# icbm_power_dpak.net
KiCad netlist of a schematic drawn in EAGLE
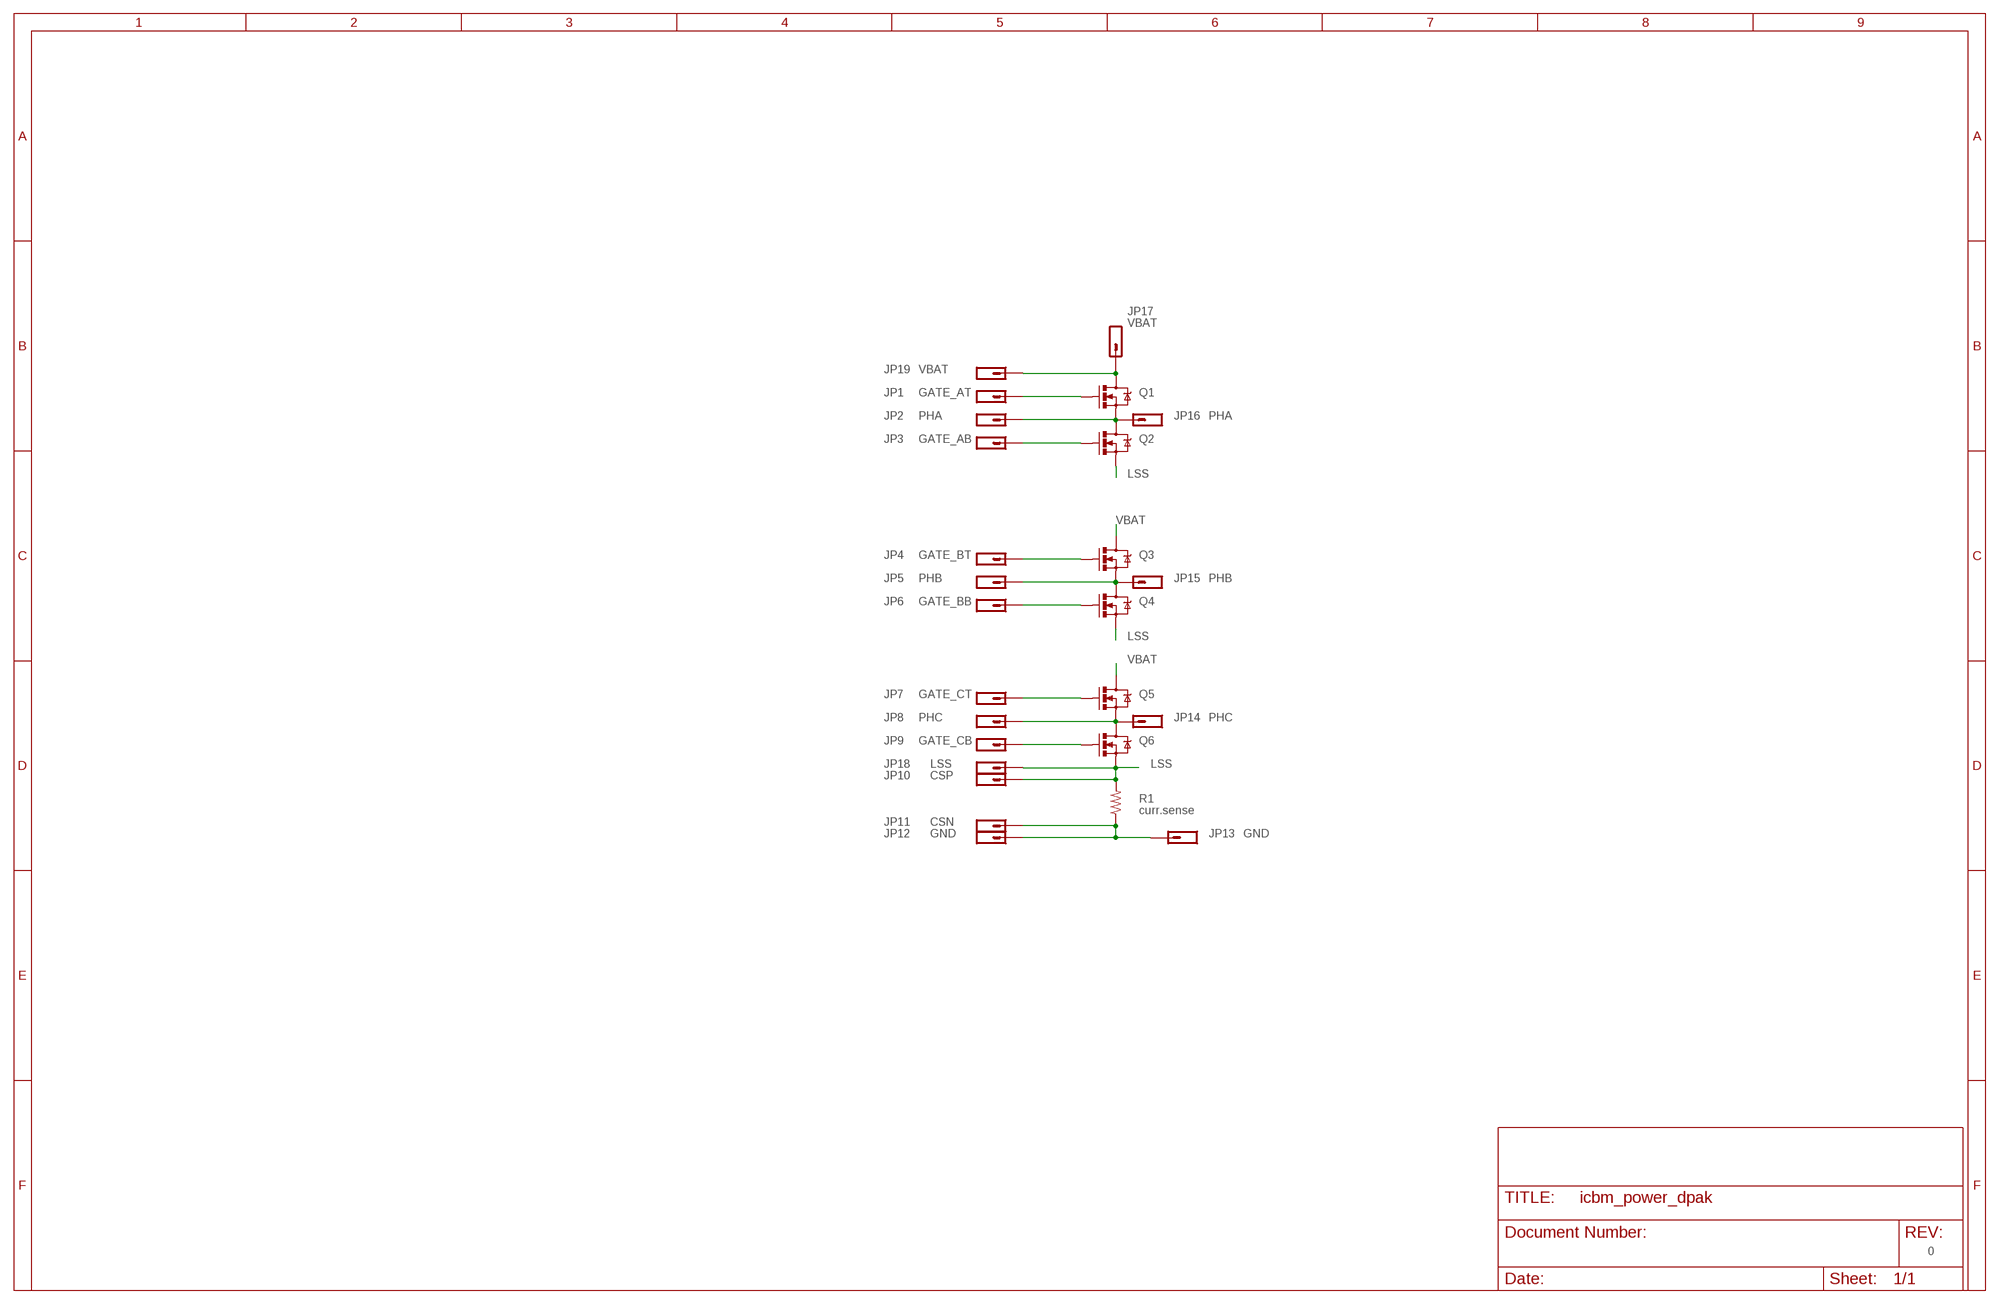
[diagram p0: schematic, sheet 1]

(export (version "E")
  (design (tool "Eeschema 10.0.6"))
  (components
    (comp (ref "JP1")
      (value "GATE_AT")
      (footprint "eagle-import:1X01_TT")
      (libsource (lib "eagle-import") (part "M01-TT"))
    )
    (comp (ref "JP2")
      (value "PHA")
      (footprint "eagle-import:1X01_TT")
      (libsource (lib "eagle-import") (part "M01-TT"))
    )
    (comp (ref "JP3")
      (value "GATE_AB")
      (footprint "eagle-import:1X01_TT")
      (libsource (lib "eagle-import") (part "M01-TT"))
    )
    (comp (ref "JP4")
      (value "GATE_BT")
      (footprint "eagle-import:1X01_TT")
      (libsource (lib "eagle-import") (part "M01-TT"))
    )
    (comp (ref "JP5")
      (value "PHB")
      (footprint "eagle-import:1X01_TT")
      (libsource (lib "eagle-import") (part "M01-TT"))
    )
    (comp (ref "JP6")
      (value "GATE_BB")
      (footprint "eagle-import:1X01_TT")
      (libsource (lib "eagle-import") (part "M01-TT"))
    )
    (comp (ref "JP7")
      (value "GATE_CT")
      (footprint "eagle-import:1X01_TT")
      (libsource (lib "eagle-import") (part "M01-TT"))
    )
    (comp (ref "JP8")
      (value "PHC")
      (footprint "eagle-import:1X01_TT")
      (libsource (lib "eagle-import") (part "M01-TT"))
    )
    (comp (ref "JP9")
      (value "GATE_CB")
      (footprint "eagle-import:1X01_TT")
      (libsource (lib "eagle-import") (part "M01-TT"))
    )
    (comp (ref "JP10")
      (value "CSP")
      (footprint "eagle-import:1X01_TT")
      (libsource (lib "eagle-import") (part "M01-TT"))
    )
    (comp (ref "JP11")
      (value "CSN")
      (footprint "eagle-import:1X01_TT")
      (libsource (lib "eagle-import") (part "M01-TT"))
    )
    (comp (ref "JP12")
      (value "GND")
      (footprint "eagle-import:1X01_TT")
      (libsource (lib "eagle-import") (part "M01-TT"))
    )
    (comp (ref "JP13")
      (value "GND")
      (footprint "eagle-import:1X01_TT")
      (libsource (lib "eagle-import") (part "M01-TT"))
    )
    (comp (ref "JP14")
      (value "PHC")
      (footprint "eagle-import:1X01_TT")
      (libsource (lib "eagle-import") (part "M01-TT"))
    )
    (comp (ref "JP15")
      (value "PHB")
      (footprint "eagle-import:1X01_TT")
      (libsource (lib "eagle-import") (part "M01-TT"))
    )
    (comp (ref "JP16")
      (value "PHA")
      (footprint "eagle-import:1X01_TT")
      (libsource (lib "eagle-import") (part "M01-TT"))
    )
    (comp (ref "JP17")
      (value "VBAT")
      (footprint "eagle-import:1X01_TT")
      (libsource (lib "eagle-import") (part "M01-TT"))
    )
    (comp (ref "JP18")
      (value "LSS")
      (footprint "eagle-import:1X01_TT")
      (libsource (lib "eagle-import") (part "M01-TT"))
    )
    (comp (ref "JP19")
      (value "VBAT")
      (footprint "eagle-import:1X01_TT")
      (libsource (lib "eagle-import") (part "M01-TT"))
    )
    (comp (ref "Q1")
      (value "MOSFET-NCHANNEL-DPAK")
      (footprint "eagle-import:DPAK")
      (libsource (lib "eagle-import") (part "MOSFET-NCHANNEL-DPAK"))
    )
    (comp (ref "Q2")
      (value "MOSFET-NCHANNEL-DPAK")
      (footprint "eagle-import:DPAK")
      (libsource (lib "eagle-import") (part "MOSFET-NCHANNEL-DPAK"))
    )
    (comp (ref "Q3")
      (value "MOSFET-NCHANNEL-DPAK")
      (footprint "eagle-import:DPAK")
      (libsource (lib "eagle-import") (part "MOSFET-NCHANNEL-DPAK"))
    )
    (comp (ref "Q4")
      (value "MOSFET-NCHANNEL-DPAK")
      (footprint "eagle-import:DPAK")
      (libsource (lib "eagle-import") (part "MOSFET-NCHANNEL-DPAK"))
    )
    (comp (ref "Q5")
      (value "MOSFET-NCHANNEL-DPAK")
      (footprint "eagle-import:DPAK")
      (libsource (lib "eagle-import") (part "MOSFET-NCHANNEL-DPAK"))
    )
    (comp (ref "Q6")
      (value "MOSFET-NCHANNEL-DPAK")
      (footprint "eagle-import:DPAK")
      (libsource (lib "eagle-import") (part "MOSFET-NCHANNEL-DPAK"))
    )
    (comp (ref "R1")
      (value "curr.sense")
      (footprint "eagle-import:2512")
      (libsource (lib "eagle-import") (part "RESISTOR-2512"))
    )
  )
  (nets
    (net (code "1") (name "/LSS") (class "Default")
      (node (ref "JP10") (pin "1") (pinfunction "1_1") (pintype "passive"))
      (node (ref "JP18") (pin "1") (pinfunction "1_1") (pintype "passive"))
      (node (ref "Q2") (pin "3") (pinfunction "S_3") (pintype "passive"))
      (node (ref "Q4") (pin "3") (pinfunction "S_3") (pintype "passive"))
      (node (ref "Q6") (pin "3") (pinfunction "S_3") (pintype "passive"))
      (node (ref "R1") (pin "P$2") (pinfunction "2_P$2") (pintype "passive"))
    )
    (net (code "2") (name "/VBAT") (class "Default")
      (node (ref "JP17") (pin "1") (pinfunction "1_1") (pintype "passive"))
      (node (ref "JP19") (pin "1") (pinfunction "1_1") (pintype "passive"))
      (node (ref "Q1") (pin "4") (pinfunction "D_4") (pintype "passive"))
      (node (ref "Q3") (pin "4") (pinfunction "D_4") (pintype "passive"))
      (node (ref "Q5") (pin "4") (pinfunction "D_4") (pintype "passive"))
    )
    (net (code "3") (name "Net-(Q1-G)") (class "Default")
      (node (ref "JP1") (pin "1") (pinfunction "1_1") (pintype "passive"))
      (node (ref "Q1") (pin "1") (pinfunction "G_1") (pintype "passive"))
    )
    (net (code "4") (name "Net-(Q1-S)") (class "Default")
      (node (ref "JP16") (pin "1") (pinfunction "1_1") (pintype "passive"))
      (node (ref "JP2") (pin "1") (pinfunction "1_1") (pintype "passive"))
      (node (ref "Q1") (pin "3") (pinfunction "S_3") (pintype "passive"))
      (node (ref "Q2") (pin "4") (pinfunction "D_4") (pintype "passive"))
    )
    (net (code "5") (name "Net-(Q2-G)") (class "Default")
      (node (ref "JP3") (pin "1") (pinfunction "1_1") (pintype "passive"))
      (node (ref "Q2") (pin "1") (pinfunction "G_1") (pintype "passive"))
    )
    (net (code "6") (name "Net-(Q3-G)") (class "Default")
      (node (ref "JP4") (pin "1") (pinfunction "1_1") (pintype "passive"))
      (node (ref "Q3") (pin "1") (pinfunction "G_1") (pintype "passive"))
    )
    (net (code "7") (name "Net-(Q3-S)") (class "Default")
      (node (ref "JP15") (pin "1") (pinfunction "1_1") (pintype "passive"))
      (node (ref "JP5") (pin "1") (pinfunction "1_1") (pintype "passive"))
      (node (ref "Q3") (pin "3") (pinfunction "S_3") (pintype "passive"))
      (node (ref "Q4") (pin "4") (pinfunction "D_4") (pintype "passive"))
    )
    (net (code "8") (name "Net-(Q4-G)") (class "Default")
      (node (ref "JP6") (pin "1") (pinfunction "1_1") (pintype "passive"))
      (node (ref "Q4") (pin "1") (pinfunction "G_1") (pintype "passive"))
    )
    (net (code "9") (name "Net-(Q5-G)") (class "Default")
      (node (ref "JP7") (pin "1") (pinfunction "1_1") (pintype "passive"))
      (node (ref "Q5") (pin "1") (pinfunction "G_1") (pintype "passive"))
    )
    (net (code "10") (name "Net-(Q5-S)") (class "Default")
      (node (ref "JP14") (pin "1") (pinfunction "1_1") (pintype "passive"))
      (node (ref "JP8") (pin "1") (pinfunction "1_1") (pintype "passive"))
      (node (ref "Q5") (pin "3") (pinfunction "S_3") (pintype "passive"))
      (node (ref "Q6") (pin "4") (pinfunction "D_4") (pintype "passive"))
    )
    (net (code "11") (name "Net-(Q6-G)") (class "Default")
      (node (ref "JP9") (pin "1") (pinfunction "1_1") (pintype "passive"))
      (node (ref "Q6") (pin "1") (pinfunction "G_1") (pintype "passive"))
    )
    (net (code "12") (name "Net-(R1-1)") (class "Default")
      (node (ref "JP11") (pin "1") (pinfunction "1_1") (pintype "passive"))
      (node (ref "JP12") (pin "1") (pinfunction "1_1") (pintype "passive"))
      (node (ref "JP13") (pin "1") (pinfunction "1_1") (pintype "passive"))
      (node (ref "R1") (pin "P$1") (pinfunction "1_P$1") (pintype "passive"))
    )
  )
)
